# etcolor.net
KiCad netlist of a schematic drawn in EAGLE
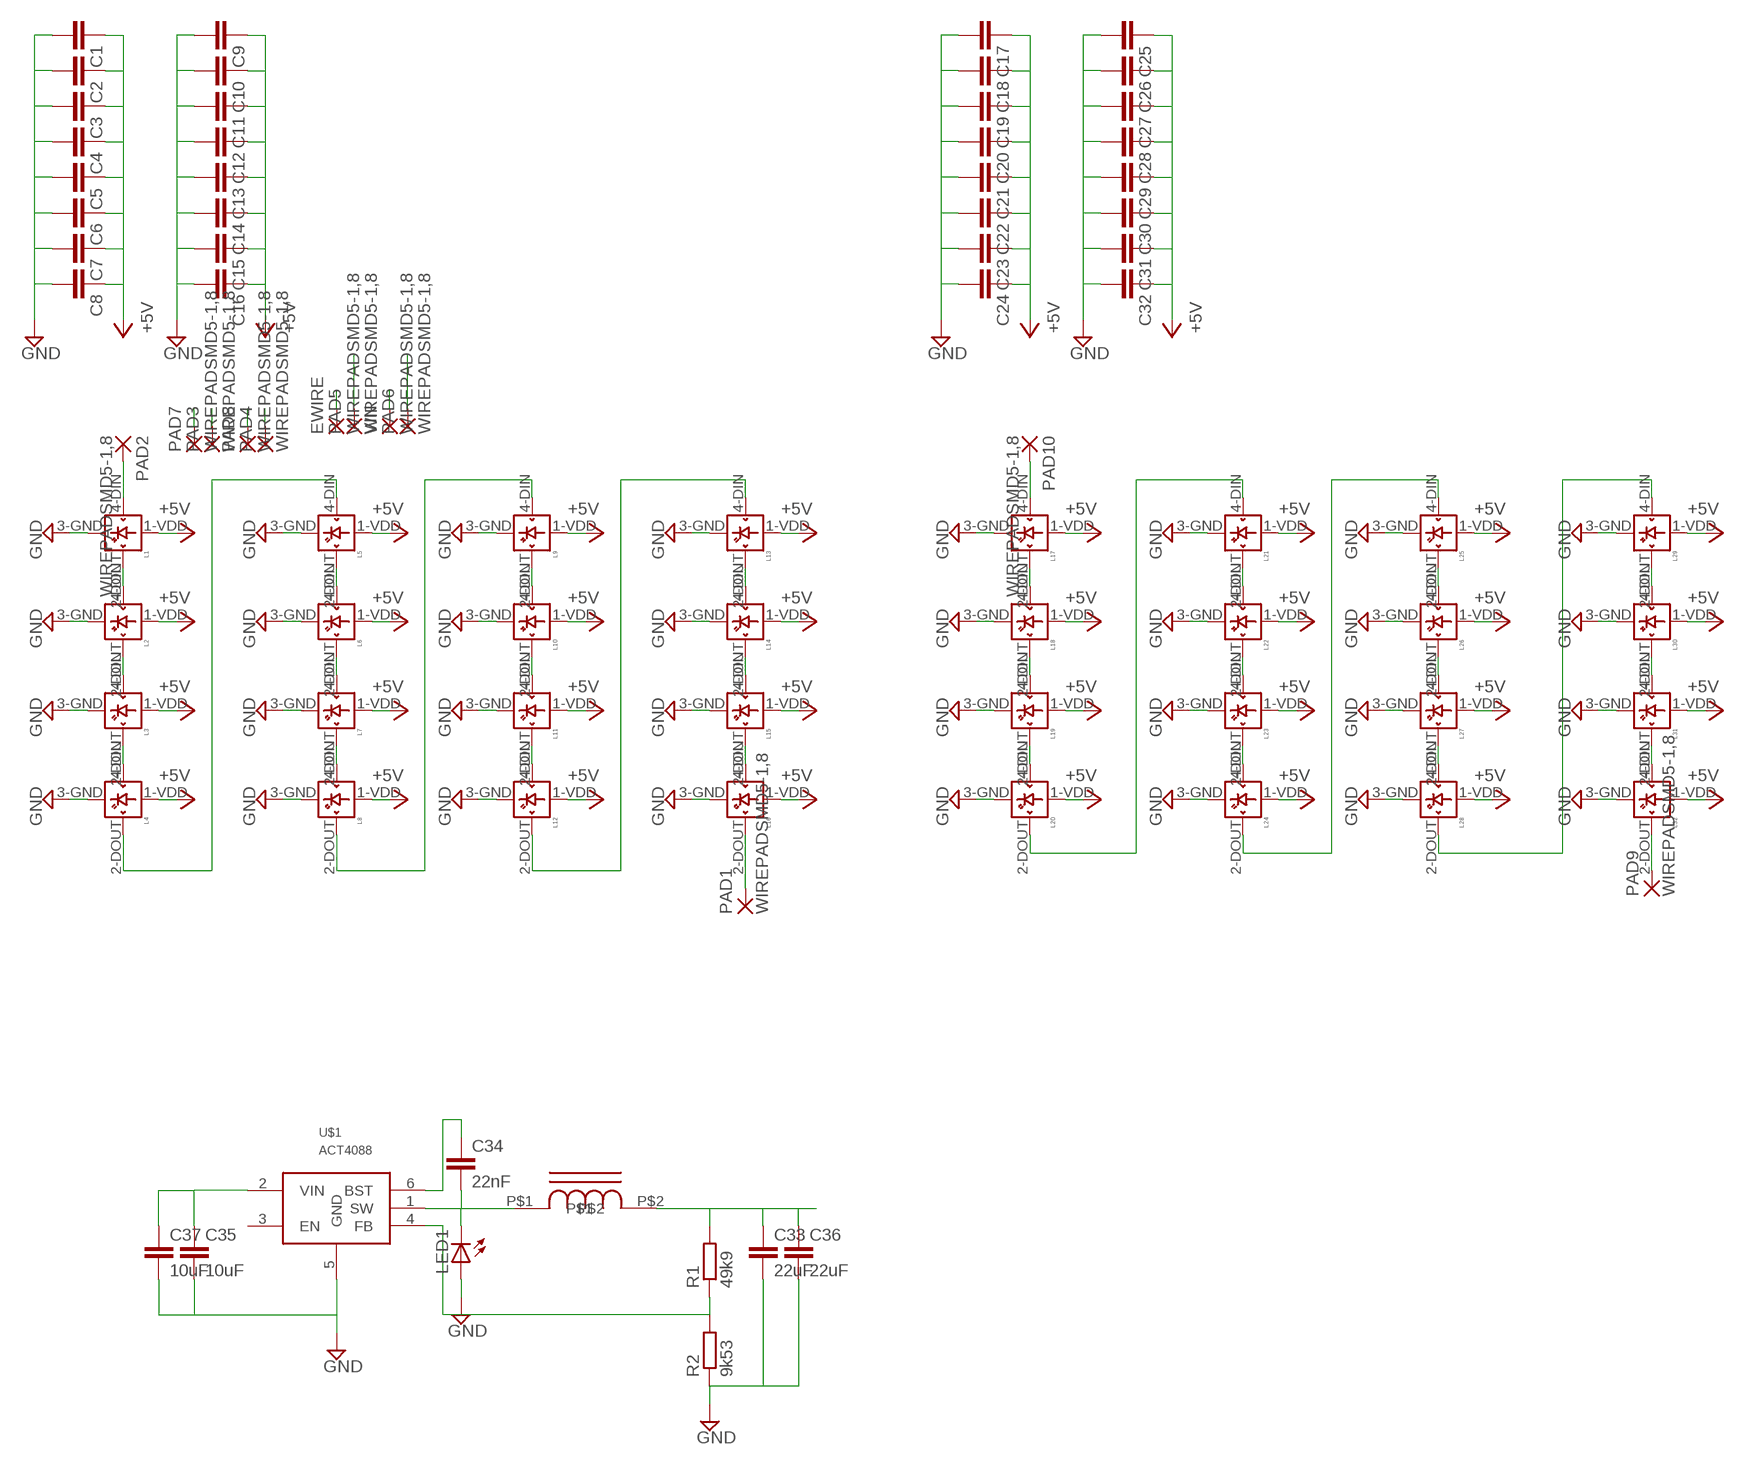
[diagram p0: schematic, sheet 1]

(export (version "E")
  (design (tool "Eeschema 10.0.6"))
  (components
    (comp (ref "C1")
      (value "C-EUC0805K")
      (footprint "eagle-import:C0805K")
      (libsource (lib "eagle-import") (part "resistor_C-EUC0805K"))
    )
    (comp (ref "C2")
      (value "C-EUC0805K")
      (footprint "eagle-import:C0805K")
      (libsource (lib "eagle-import") (part "resistor_C-EUC0805K"))
    )
    (comp (ref "C3")
      (value "C-EUC0805K")
      (footprint "eagle-import:C0805K")
      (libsource (lib "eagle-import") (part "resistor_C-EUC0805K"))
    )
    (comp (ref "C4")
      (value "C-EUC0805K")
      (footprint "eagle-import:C0805K")
      (libsource (lib "eagle-import") (part "resistor_C-EUC0805K"))
    )
    (comp (ref "C5")
      (value "C-EUC0805K")
      (footprint "eagle-import:C0805K")
      (libsource (lib "eagle-import") (part "resistor_C-EUC0805K"))
    )
    (comp (ref "C6")
      (value "C-EUC0805K")
      (footprint "eagle-import:C0805K")
      (libsource (lib "eagle-import") (part "resistor_C-EUC0805K"))
    )
    (comp (ref "C7")
      (value "C-EUC0805K")
      (footprint "eagle-import:C0805K")
      (libsource (lib "eagle-import") (part "resistor_C-EUC0805K"))
    )
    (comp (ref "C8")
      (value "C-EUC0805K")
      (footprint "eagle-import:C0805K")
      (libsource (lib "eagle-import") (part "resistor_C-EUC0805K"))
    )
    (comp (ref "C9")
      (value "C-EUC0805K")
      (footprint "eagle-import:C0805K")
      (libsource (lib "eagle-import") (part "resistor_C-EUC0805K"))
    )
    (comp (ref "C10")
      (value "C-EUC0805K")
      (footprint "eagle-import:C0805K")
      (libsource (lib "eagle-import") (part "resistor_C-EUC0805K"))
    )
    (comp (ref "C11")
      (value "C-EUC0805K")
      (footprint "eagle-import:C0805K")
      (libsource (lib "eagle-import") (part "resistor_C-EUC0805K"))
    )
    (comp (ref "C12")
      (value "C-EUC0805K")
      (footprint "eagle-import:C0805K")
      (libsource (lib "eagle-import") (part "resistor_C-EUC0805K"))
    )
    (comp (ref "C13")
      (value "C-EUC0805K")
      (footprint "eagle-import:C0805K")
      (libsource (lib "eagle-import") (part "resistor_C-EUC0805K"))
    )
    (comp (ref "C14")
      (value "C-EUC0805K")
      (footprint "eagle-import:C0805K")
      (libsource (lib "eagle-import") (part "resistor_C-EUC0805K"))
    )
    (comp (ref "C15")
      (value "C-EUC0805K")
      (footprint "eagle-import:C0805K")
      (libsource (lib "eagle-import") (part "resistor_C-EUC0805K"))
    )
    (comp (ref "C16")
      (value "C-EUC0805K")
      (footprint "eagle-import:C0805K")
      (libsource (lib "eagle-import") (part "resistor_C-EUC0805K"))
    )
    (comp (ref "C17")
      (value "C-EUC0805K")
      (footprint "eagle-import:C0805K")
      (libsource (lib "eagle-import") (part "resistor_C-EUC0805K"))
    )
    (comp (ref "C18")
      (value "C-EUC0805K")
      (footprint "eagle-import:C0805K")
      (libsource (lib "eagle-import") (part "resistor_C-EUC0805K"))
    )
    (comp (ref "C19")
      (value "C-EUC0805K")
      (footprint "eagle-import:C0805K")
      (libsource (lib "eagle-import") (part "resistor_C-EUC0805K"))
    )
    (comp (ref "C20")
      (value "C-EUC0805K")
      (footprint "eagle-import:C0805K")
      (libsource (lib "eagle-import") (part "resistor_C-EUC0805K"))
    )
    (comp (ref "C21")
      (value "C-EUC0805K")
      (footprint "eagle-import:C0805K")
      (libsource (lib "eagle-import") (part "resistor_C-EUC0805K"))
    )
    (comp (ref "C22")
      (value "C-EUC0805K")
      (footprint "eagle-import:C0805K")
      (libsource (lib "eagle-import") (part "resistor_C-EUC0805K"))
    )
    (comp (ref "C23")
      (value "C-EUC0805K")
      (footprint "eagle-import:C0805K")
      (libsource (lib "eagle-import") (part "resistor_C-EUC0805K"))
    )
    (comp (ref "C24")
      (value "C-EUC0805K")
      (footprint "eagle-import:C0805K")
      (libsource (lib "eagle-import") (part "resistor_C-EUC0805K"))
    )
    (comp (ref "C25")
      (value "C-EUC0805K")
      (footprint "eagle-import:C0805K")
      (libsource (lib "eagle-import") (part "resistor_C-EUC0805K"))
    )
    (comp (ref "C26")
      (value "C-EUC0805K")
      (footprint "eagle-import:C0805K")
      (libsource (lib "eagle-import") (part "resistor_C-EUC0805K"))
    )
    (comp (ref "C27")
      (value "C-EUC0805K")
      (footprint "eagle-import:C0805K")
      (libsource (lib "eagle-import") (part "resistor_C-EUC0805K"))
    )
    (comp (ref "C28")
      (value "C-EUC0805K")
      (footprint "eagle-import:C0805K")
      (libsource (lib "eagle-import") (part "resistor_C-EUC0805K"))
    )
    (comp (ref "C29")
      (value "C-EUC0805K")
      (footprint "eagle-import:C0805K")
      (libsource (lib "eagle-import") (part "resistor_C-EUC0805K"))
    )
    (comp (ref "C30")
      (value "C-EUC0805K")
      (footprint "eagle-import:C0805K")
      (libsource (lib "eagle-import") (part "resistor_C-EUC0805K"))
    )
    (comp (ref "C31")
      (value "C-EUC0805K")
      (footprint "eagle-import:C0805K")
      (libsource (lib "eagle-import") (part "resistor_C-EUC0805K"))
    )
    (comp (ref "C32")
      (value "C-EUC0805K")
      (footprint "eagle-import:C0805K")
      (libsource (lib "eagle-import") (part "resistor_C-EUC0805K"))
    )
    (comp (ref "C33")
      (value "22uF")
      (footprint "eagle-import:C1210")
      (libsource (lib "eagle-import") (part "C-EUC1210"))
    )
    (comp (ref "C34")
      (value "22nF")
      (footprint "eagle-import:C0805")
      (libsource (lib "eagle-import") (part "resistor_C-EUC0805"))
    )
    (comp (ref "C35")
      (value "10uF")
      (footprint "eagle-import:C1210")
      (libsource (lib "eagle-import") (part "C-EUC1210"))
    )
    (comp (ref "C36")
      (value "22uF")
      (footprint "eagle-import:C1210")
      (libsource (lib "eagle-import") (part "C-EUC1210"))
    )
    (comp (ref "C37")
      (value "10uF")
      (footprint "eagle-import:C1210")
      (libsource (lib "eagle-import") (part "C-EUC1210"))
    )
    (comp (ref "EWIRE")
      (value "WIREPADSMD5-1,8")
      (footprint "eagle-import:5-1,8")
      (libsource (lib "eagle-import") (part "WIREPADSMD5-1,8"))
    )
    (comp (ref "L1")
      (value "WS2812B")
      (footprint "eagle-import:WS2812B")
      (libsource (lib "eagle-import") (part "WS2812B"))
    )
    (comp (ref "L2")
      (value "WS2812B")
      (footprint "eagle-import:WS2812B")
      (libsource (lib "eagle-import") (part "WS2812B"))
    )
    (comp (ref "L3")
      (value "WS2812B")
      (footprint "eagle-import:WS2812B")
      (libsource (lib "eagle-import") (part "WS2812B"))
    )
    (comp (ref "L4")
      (value "WS2812B")
      (footprint "eagle-import:WS2812B")
      (libsource (lib "eagle-import") (part "WS2812B"))
    )
    (comp (ref "L5")
      (value "WS2812B")
      (footprint "eagle-import:WS2812B")
      (libsource (lib "eagle-import") (part "WS2812B"))
    )
    (comp (ref "L6")
      (value "WS2812B")
      (footprint "eagle-import:WS2812B")
      (libsource (lib "eagle-import") (part "WS2812B"))
    )
    (comp (ref "L7")
      (value "WS2812B")
      (footprint "eagle-import:WS2812B")
      (libsource (lib "eagle-import") (part "WS2812B"))
    )
    (comp (ref "L8")
      (value "WS2812B")
      (footprint "eagle-import:WS2812B")
      (libsource (lib "eagle-import") (part "WS2812B"))
    )
    (comp (ref "L9")
      (value "WS2812B")
      (footprint "eagle-import:WS2812B")
      (libsource (lib "eagle-import") (part "WS2812B"))
    )
    (comp (ref "L10")
      (value "WS2812B")
      (footprint "eagle-import:WS2812B")
      (libsource (lib "eagle-import") (part "WS2812B"))
    )
    (comp (ref "L11")
      (value "WS2812B")
      (footprint "eagle-import:WS2812B")
      (libsource (lib "eagle-import") (part "WS2812B"))
    )
    (comp (ref "L12")
      (value "WS2812B")
      (footprint "eagle-import:WS2812B")
      (libsource (lib "eagle-import") (part "WS2812B"))
    )
    (comp (ref "L13")
      (value "WS2812B")
      (footprint "eagle-import:WS2812B")
      (libsource (lib "eagle-import") (part "WS2812B"))
    )
    (comp (ref "L14")
      (value "WS2812B")
      (footprint "eagle-import:WS2812B")
      (libsource (lib "eagle-import") (part "WS2812B"))
    )
    (comp (ref "L15")
      (value "WS2812B")
      (footprint "eagle-import:WS2812B")
      (libsource (lib "eagle-import") (part "WS2812B"))
    )
    (comp (ref "L16")
      (value "WS2812B")
      (footprint "eagle-import:WS2812B")
      (libsource (lib "eagle-import") (part "WS2812B"))
    )
    (comp (ref "L17")
      (value "WS2812B")
      (footprint "eagle-import:WS2812B")
      (libsource (lib "eagle-import") (part "WS2812B"))
    )
    (comp (ref "L18")
      (value "WS2812B")
      (footprint "eagle-import:WS2812B")
      (libsource (lib "eagle-import") (part "WS2812B"))
    )
    (comp (ref "L19")
      (value "WS2812B")
      (footprint "eagle-import:WS2812B")
      (libsource (lib "eagle-import") (part "WS2812B"))
    )
    (comp (ref "L20")
      (value "WS2812B")
      (footprint "eagle-import:WS2812B")
      (libsource (lib "eagle-import") (part "WS2812B"))
    )
    (comp (ref "L21")
      (value "WS2812B")
      (footprint "eagle-import:WS2812B")
      (libsource (lib "eagle-import") (part "WS2812B"))
    )
    (comp (ref "L22")
      (value "WS2812B")
      (footprint "eagle-import:WS2812B")
      (libsource (lib "eagle-import") (part "WS2812B"))
    )
    (comp (ref "L23")
      (value "WS2812B")
      (footprint "eagle-import:WS2812B")
      (libsource (lib "eagle-import") (part "WS2812B"))
    )
    (comp (ref "L24")
      (value "WS2812B")
      (footprint "eagle-import:WS2812B")
      (libsource (lib "eagle-import") (part "WS2812B"))
    )
    (comp (ref "L25")
      (value "WS2812B")
      (footprint "eagle-import:WS2812B")
      (libsource (lib "eagle-import") (part "WS2812B"))
    )
    (comp (ref "L26")
      (value "WS2812B")
      (footprint "eagle-import:WS2812B")
      (libsource (lib "eagle-import") (part "WS2812B"))
    )
    (comp (ref "L27")
      (value "WS2812B")
      (footprint "eagle-import:WS2812B")
      (libsource (lib "eagle-import") (part "WS2812B"))
    )
    (comp (ref "L28")
      (value "WS2812B")
      (footprint "eagle-import:WS2812B")
      (libsource (lib "eagle-import") (part "WS2812B"))
    )
    (comp (ref "L29")
      (value "WS2812B")
      (footprint "eagle-import:WS2812B")
      (libsource (lib "eagle-import") (part "WS2812B"))
    )
    (comp (ref "L30")
      (value "WS2812B")
      (footprint "eagle-import:WS2812B")
      (libsource (lib "eagle-import") (part "WS2812B"))
    )
    (comp (ref "L31")
      (value "WS2812B")
      (footprint "eagle-import:WS2812B")
      (libsource (lib "eagle-import") (part "WS2812B"))
    )
    (comp (ref "L32")
      (value "WS2812B")
      (footprint "eagle-import:WS2812B")
      (libsource (lib "eagle-import") (part "WS2812B"))
    )
    (comp (ref "LED1")
      (value "LED1206")
      (footprint "eagle-import:LED-1206")
      (libsource (lib "eagle-import") (part "LED1206"))
    )
    (comp (ref "PAD1")
      (value "WIREPADSMD5-1,8")
      (footprint "eagle-import:5-1,8")
      (libsource (lib "eagle-import") (part "WIREPADSMD5-1,8"))
    )
    (comp (ref "PAD2")
      (value "WIREPADSMD5-1,8")
      (footprint "eagle-import:5-1,8")
      (libsource (lib "eagle-import") (part "WIREPADSMD5-1,8"))
    )
    (comp (ref "PAD3")
      (value "WIREPADSMD5-1,8")
      (footprint "eagle-import:5-1,8")
      (libsource (lib "eagle-import") (part "WIREPADSMD5-1,8"))
    )
    (comp (ref "PAD4")
      (value "WIREPADSMD5-1,8")
      (footprint "eagle-import:5-1,8")
      (libsource (lib "eagle-import") (part "WIREPADSMD5-1,8"))
    )
    (comp (ref "PAD5")
      (value "WIREPADSMD5-1,8")
      (footprint "eagle-import:5-1,8")
      (libsource (lib "eagle-import") (part "WIREPADSMD5-1,8"))
    )
    (comp (ref "PAD6")
      (value "WIREPADSMD5-1,8")
      (footprint "eagle-import:5-1,8")
      (libsource (lib "eagle-import") (part "WIREPADSMD5-1,8"))
    )
    (comp (ref "PAD7")
      (value "WIREPADSMD5-1,8")
      (footprint "eagle-import:5-1,8")
      (libsource (lib "eagle-import") (part "WIREPADSMD5-1,8"))
    )
    (comp (ref "PAD8")
      (value "WIREPADSMD5-1,8")
      (footprint "eagle-import:5-1,8")
      (libsource (lib "eagle-import") (part "WIREPADSMD5-1,8"))
    )
    (comp (ref "PAD9")
      (value "WIREPADSMD5-1,8")
      (footprint "eagle-import:5-1,8")
      (libsource (lib "eagle-import") (part "WIREPADSMD5-1,8"))
    )
    (comp (ref "PAD10")
      (value "WIREPADSMD5-1,8")
      (footprint "eagle-import:5-1,8")
      (libsource (lib "eagle-import") (part "WIREPADSMD5-1,8"))
    )
    (comp (ref "R1")
      (value "49k9")
      (footprint "eagle-import:M0805")
      (libsource (lib "eagle-import") (part "R-EU_M0805"))
    )
    (comp (ref "R2")
      (value "9k53")
      (footprint "eagle-import:M0805")
      (libsource (lib "eagle-import") (part "R-EU_M0805"))
    )
    (comp (ref "U$1")
      (value "ACT4088")
      (footprint "eagle-import:SOT23-6")
      (libsource (lib "eagle-import") (part "ACT4088"))
    )
    (comp (ref "U$2")
      (value "INDUCTOR")
      (footprint "eagle-import:6060")
      (libsource (lib "eagle-import") (part "INDUCTOR"))
    )
    (comp (ref "VIN")
      (value "WIREPADSMD5-1,8")
      (footprint "eagle-import:5-1,8")
      (libsource (lib "eagle-import") (part "WIREPADSMD5-1,8"))
    )
  )
  (nets
    (net (code "1") (name "+5V") (class "Default")
      (node (ref "C1") (pin "1") (pinfunction "1_1") (pintype "passive"))
      (node (ref "C10") (pin "1") (pinfunction "1_1") (pintype "passive"))
      (node (ref "C11") (pin "1") (pinfunction "1_1") (pintype "passive"))
      (node (ref "C12") (pin "1") (pinfunction "1_1") (pintype "passive"))
      (node (ref "C13") (pin "1") (pinfunction "1_1") (pintype "passive"))
      (node (ref "C14") (pin "1") (pinfunction "1_1") (pintype "passive"))
      (node (ref "C15") (pin "1") (pinfunction "1_1") (pintype "passive"))
      (node (ref "C16") (pin "1") (pinfunction "1_1") (pintype "passive"))
      (node (ref "C17") (pin "1") (pinfunction "1_1") (pintype "passive"))
      (node (ref "C18") (pin "1") (pinfunction "1_1") (pintype "passive"))
      (node (ref "C19") (pin "1") (pinfunction "1_1") (pintype "passive"))
      (node (ref "C2") (pin "1") (pinfunction "1_1") (pintype "passive"))
      (node (ref "C20") (pin "1") (pinfunction "1_1") (pintype "passive"))
      (node (ref "C21") (pin "1") (pinfunction "1_1") (pintype "passive"))
      (node (ref "C22") (pin "1") (pinfunction "1_1") (pintype "passive"))
      (node (ref "C23") (pin "1") (pinfunction "1_1") (pintype "passive"))
      (node (ref "C24") (pin "1") (pinfunction "1_1") (pintype "passive"))
      (node (ref "C25") (pin "1") (pinfunction "1_1") (pintype "passive"))
      (node (ref "C26") (pin "1") (pinfunction "1_1") (pintype "passive"))
      (node (ref "C27") (pin "1") (pinfunction "1_1") (pintype "passive"))
      (node (ref "C28") (pin "1") (pinfunction "1_1") (pintype "passive"))
      (node (ref "C29") (pin "1") (pinfunction "1_1") (pintype "passive"))
      (node (ref "C3") (pin "1") (pinfunction "1_1") (pintype "passive"))
      (node (ref "C30") (pin "1") (pinfunction "1_1") (pintype "passive"))
      (node (ref "C31") (pin "1") (pinfunction "1_1") (pintype "passive"))
      (node (ref "C32") (pin "1") (pinfunction "1_1") (pintype "passive"))
      (node (ref "C33") (pin "1") (pinfunction "1_1") (pintype "passive"))
      (node (ref "C36") (pin "1") (pinfunction "1_1") (pintype "passive"))
      (node (ref "C4") (pin "1") (pinfunction "1_1") (pintype "passive"))
      (node (ref "C5") (pin "1") (pinfunction "1_1") (pintype "passive"))
      (node (ref "C6") (pin "1") (pinfunction "1_1") (pintype "passive"))
      (node (ref "C7") (pin "1") (pinfunction "1_1") (pintype "passive"))
      (node (ref "C8") (pin "1") (pinfunction "1_1") (pintype "passive"))
      (node (ref "C9") (pin "1") (pinfunction "1_1") (pintype "passive"))
      (node (ref "L1") (pin "1-VDD") (pinfunction "VDD_1-VDD") (pintype "bidirectional"))
      (node (ref "L10") (pin "1-VDD") (pinfunction "VDD_1-VDD") (pintype "bidirectional"))
      (node (ref "L11") (pin "1-VDD") (pinfunction "VDD_1-VDD") (pintype "bidirectional"))
      (node (ref "L12") (pin "1-VDD") (pinfunction "VDD_1-VDD") (pintype "bidirectional"))
      (node (ref "L13") (pin "1-VDD") (pinfunction "VDD_1-VDD") (pintype "bidirectional"))
      (node (ref "L14") (pin "1-VDD") (pinfunction "VDD_1-VDD") (pintype "bidirectional"))
      (node (ref "L15") (pin "1-VDD") (pinfunction "VDD_1-VDD") (pintype "bidirectional"))
      (node (ref "L16") (pin "1-VDD") (pinfunction "VDD_1-VDD") (pintype "bidirectional"))
      (node (ref "L17") (pin "1-VDD") (pinfunction "VDD_1-VDD") (pintype "bidirectional"))
      (node (ref "L18") (pin "1-VDD") (pinfunction "VDD_1-VDD") (pintype "bidirectional"))
      (node (ref "L19") (pin "1-VDD") (pinfunction "VDD_1-VDD") (pintype "bidirectional"))
      (node (ref "L2") (pin "1-VDD") (pinfunction "VDD_1-VDD") (pintype "bidirectional"))
      (node (ref "L20") (pin "1-VDD") (pinfunction "VDD_1-VDD") (pintype "bidirectional"))
      (node (ref "L21") (pin "1-VDD") (pinfunction "VDD_1-VDD") (pintype "bidirectional"))
      (node (ref "L22") (pin "1-VDD") (pinfunction "VDD_1-VDD") (pintype "bidirectional"))
      (node (ref "L23") (pin "1-VDD") (pinfunction "VDD_1-VDD") (pintype "bidirectional"))
      (node (ref "L24") (pin "1-VDD") (pinfunction "VDD_1-VDD") (pintype "bidirectional"))
      (node (ref "L25") (pin "1-VDD") (pinfunction "VDD_1-VDD") (pintype "bidirectional"))
      (node (ref "L26") (pin "1-VDD") (pinfunction "VDD_1-VDD") (pintype "bidirectional"))
      (node (ref "L27") (pin "1-VDD") (pinfunction "VDD_1-VDD") (pintype "bidirectional"))
      (node (ref "L28") (pin "1-VDD") (pinfunction "VDD_1-VDD") (pintype "bidirectional"))
      (node (ref "L29") (pin "1-VDD") (pinfunction "VDD_1-VDD") (pintype "bidirectional"))
      (node (ref "L3") (pin "1-VDD") (pinfunction "VDD_1-VDD") (pintype "bidirectional"))
      (node (ref "L30") (pin "1-VDD") (pinfunction "VDD_1-VDD") (pintype "bidirectional"))
      (node (ref "L31") (pin "1-VDD") (pinfunction "VDD_1-VDD") (pintype "bidirectional"))
      (node (ref "L32") (pin "1-VDD") (pinfunction "VDD_1-VDD") (pintype "bidirectional"))
      (node (ref "L4") (pin "1-VDD") (pinfunction "VDD_1-VDD") (pintype "bidirectional"))
      (node (ref "L5") (pin "1-VDD") (pinfunction "VDD_1-VDD") (pintype "bidirectional"))
      (node (ref "L6") (pin "1-VDD") (pinfunction "VDD_1-VDD") (pintype "bidirectional"))
      (node (ref "L7") (pin "1-VDD") (pinfunction "VDD_1-VDD") (pintype "bidirectional"))
      (node (ref "L8") (pin "1-VDD") (pinfunction "VDD_1-VDD") (pintype "bidirectional"))
      (node (ref "L9") (pin "1-VDD") (pinfunction "VDD_1-VDD") (pintype "bidirectional"))
      (node (ref "R1") (pin "2") (pinfunction "2_2") (pintype "passive"))
      (node (ref "U$2") (pin "P$2") (pinfunction "P$2_P$2") (pintype "bidirectional"))
    )
    (net (code "2") (name "/VIN") (class "Default")
      (node (ref "C35") (pin "1") (pinfunction "1_1") (pintype "passive"))
      (node (ref "C37") (pin "1") (pinfunction "1_1") (pintype "passive"))
      (node (ref "EWIRE") (pin "1") (pinfunction "P_1") (pintype "passive"))
      (node (ref "PAD5") (pin "1") (pinfunction "P_1") (pintype "passive"))
      (node (ref "PAD6") (pin "1") (pinfunction "P_1") (pintype "passive"))
      (node (ref "U$1") (pin "2") (pinfunction "VIN_2") (pintype "bidirectional"))
      (node (ref "VIN") (pin "1") (pinfunction "P_1") (pintype "passive"))
    )
    (net (code "3") (name "GND") (class "Default")
      (node (ref "C1") (pin "2") (pinfunction "2_2") (pintype "passive"))
      (node (ref "C10") (pin "2") (pinfunction "2_2") (pintype "passive"))
      (node (ref "C11") (pin "2") (pinfunction "2_2") (pintype "passive"))
      (node (ref "C12") (pin "2") (pinfunction "2_2") (pintype "passive"))
      (node (ref "C13") (pin "2") (pinfunction "2_2") (pintype "passive"))
      (node (ref "C14") (pin "2") (pinfunction "2_2") (pintype "passive"))
      (node (ref "C15") (pin "2") (pinfunction "2_2") (pintype "passive"))
      (node (ref "C16") (pin "2") (pinfunction "2_2") (pintype "passive"))
      (node (ref "C17") (pin "2") (pinfunction "2_2") (pintype "passive"))
      (node (ref "C18") (pin "2") (pinfunction "2_2") (pintype "passive"))
      (node (ref "C19") (pin "2") (pinfunction "2_2") (pintype "passive"))
      (node (ref "C2") (pin "2") (pinfunction "2_2") (pintype "passive"))
      (node (ref "C20") (pin "2") (pinfunction "2_2") (pintype "passive"))
      (node (ref "C21") (pin "2") (pinfunction "2_2") (pintype "passive"))
      (node (ref "C22") (pin "2") (pinfunction "2_2") (pintype "passive"))
      (node (ref "C23") (pin "2") (pinfunction "2_2") (pintype "passive"))
      (node (ref "C24") (pin "2") (pinfunction "2_2") (pintype "passive"))
      (node (ref "C25") (pin "2") (pinfunction "2_2") (pintype "passive"))
      (node (ref "C26") (pin "2") (pinfunction "2_2") (pintype "passive"))
      (node (ref "C27") (pin "2") (pinfunction "2_2") (pintype "passive"))
      (node (ref "C28") (pin "2") (pinfunction "2_2") (pintype "passive"))
      (node (ref "C29") (pin "2") (pinfunction "2_2") (pintype "passive"))
      (node (ref "C3") (pin "2") (pinfunction "2_2") (pintype "passive"))
      (node (ref "C30") (pin "2") (pinfunction "2_2") (pintype "passive"))
      (node (ref "C31") (pin "2") (pinfunction "2_2") (pintype "passive"))
      (node (ref "C32") (pin "2") (pinfunction "2_2") (pintype "passive"))
      (node (ref "C33") (pin "2") (pinfunction "2_2") (pintype "passive"))
      (node (ref "C35") (pin "2") (pinfunction "2_2") (pintype "passive"))
      (node (ref "C36") (pin "2") (pinfunction "2_2") (pintype "passive"))
      (node (ref "C37") (pin "2") (pinfunction "2_2") (pintype "passive"))
      (node (ref "C4") (pin "2") (pinfunction "2_2") (pintype "passive"))
      (node (ref "C5") (pin "2") (pinfunction "2_2") (pintype "passive"))
      (node (ref "C6") (pin "2") (pinfunction "2_2") (pintype "passive"))
      (node (ref "C7") (pin "2") (pinfunction "2_2") (pintype "passive"))
      (node (ref "C8") (pin "2") (pinfunction "2_2") (pintype "passive"))
      (node (ref "C9") (pin "2") (pinfunction "2_2") (pintype "passive"))
      (node (ref "L1") (pin "3-GND") (pinfunction "GND_3-GND") (pintype "bidirectional"))
      (node (ref "L10") (pin "3-GND") (pinfunction "GND_3-GND") (pintype "bidirectional"))
      (node (ref "L11") (pin "3-GND") (pinfunction "GND_3-GND") (pintype "bidirectional"))
      (node (ref "L12") (pin "3-GND") (pinfunction "GND_3-GND") (pintype "bidirectional"))
      (node (ref "L13") (pin "3-GND") (pinfunction "GND_3-GND") (pintype "bidirectional"))
      (node (ref "L14") (pin "3-GND") (pinfunction "GND_3-GND") (pintype "bidirectional"))
      (node (ref "L15") (pin "3-GND") (pinfunction "GND_3-GND") (pintype "bidirectional"))
      (node (ref "L16") (pin "3-GND") (pinfunction "GND_3-GND") (pintype "bidirectional"))
      (node (ref "L17") (pin "3-GND") (pinfunction "GND_3-GND") (pintype "bidirectional"))
      (node (ref "L18") (pin "3-GND") (pinfunction "GND_3-GND") (pintype "bidirectional"))
      (node (ref "L19") (pin "3-GND") (pinfunction "GND_3-GND") (pintype "bidirectional"))
      (node (ref "L2") (pin "3-GND") (pinfunction "GND_3-GND") (pintype "bidirectional"))
      (node (ref "L20") (pin "3-GND") (pinfunction "GND_3-GND") (pintype "bidirectional"))
      (node (ref "L21") (pin "3-GND") (pinfunction "GND_3-GND") (pintype "bidirectional"))
      (node (ref "L22") (pin "3-GND") (pinfunction "GND_3-GND") (pintype "bidirectional"))
      (node (ref "L23") (pin "3-GND") (pinfunction "GND_3-GND") (pintype "bidirectional"))
      (node (ref "L24") (pin "3-GND") (pinfunction "GND_3-GND") (pintype "bidirectional"))
      (node (ref "L25") (pin "3-GND") (pinfunction "GND_3-GND") (pintype "bidirectional"))
      (node (ref "L26") (pin "3-GND") (pinfunction "GND_3-GND") (pintype "bidirectional"))
      (node (ref "L27") (pin "3-GND") (pinfunction "GND_3-GND") (pintype "bidirectional"))
      (node (ref "L28") (pin "3-GND") (pinfunction "GND_3-GND") (pintype "bidirectional"))
      (node (ref "L29") (pin "3-GND") (pinfunction "GND_3-GND") (pintype "bidirectional"))
      (node (ref "L3") (pin "3-GND") (pinfunction "GND_3-GND") (pintype "bidirectional"))
      (node (ref "L30") (pin "3-GND") (pinfunction "GND_3-GND") (pintype "bidirectional"))
      (node (ref "L31") (pin "3-GND") (pinfunction "GND_3-GND") (pintype "bidirectional"))
      (node (ref "L32") (pin "3-GND") (pinfunction "GND_3-GND") (pintype "bidirectional"))
      (node (ref "L4") (pin "3-GND") (pinfunction "GND_3-GND") (pintype "bidirectional"))
      (node (ref "L5") (pin "3-GND") (pinfunction "GND_3-GND") (pintype "bidirectional"))
      (node (ref "L6") (pin "3-GND") (pinfunction "GND_3-GND") (pintype "bidirectional"))
      (node (ref "L7") (pin "3-GND") (pinfunction "GND_3-GND") (pintype "bidirectional"))
      (node (ref "L8") (pin "3-GND") (pinfunction "GND_3-GND") (pintype "bidirectional"))
      (node (ref "L9") (pin "3-GND") (pinfunction "GND_3-GND") (pintype "bidirectional"))
      (node (ref "LED1") (pin "A") (pinfunction "A_A") (pintype "passive"))
      (node (ref "PAD3") (pin "1") (pinfunction "P_1") (pintype "passive"))
      (node (ref "PAD4") (pin "1") (pinfunction "P_1") (pintype "passive"))
      (node (ref "PAD7") (pin "1") (pinfunction "P_1") (pintype "passive"))
      (node (ref "PAD8") (pin "1") (pinfunction "P_1") (pintype "passive"))
      (node (ref "R2") (pin "1") (pinfunction "1_1") (pintype "passive"))
      (node (ref "U$1") (pin "5") (pinfunction "GND_5") (pintype "bidirectional"))
    )
    (net (code "4") (name "Net-(L1-DIN)") (class "Default")
      (node (ref "L1") (pin "4-DIN") (pinfunction "DIN_4-DIN") (pintype "input"))
      (node (ref "PAD2") (pin "1") (pinfunction "P_1") (pintype "passive"))
    )
    (net (code "5") (name "Net-(L1-DOUT)") (class "Default")
      (node (ref "L1") (pin "2-DOUT") (pinfunction "DOUT_2-DOUT") (pintype "output"))
      (node (ref "L2") (pin "4-DIN") (pinfunction "DIN_4-DIN") (pintype "input"))
    )
    (net (code "6") (name "Net-(L2-DOUT)") (class "Default")
      (node (ref "L2") (pin "2-DOUT") (pinfunction "DOUT_2-DOUT") (pintype "output"))
      (node (ref "L3") (pin "4-DIN") (pinfunction "DIN_4-DIN") (pintype "input"))
    )
    (net (code "7") (name "Net-(L3-DOUT)") (class "Default")
      (node (ref "L3") (pin "2-DOUT") (pinfunction "DOUT_2-DOUT") (pintype "output"))
      (node (ref "L4") (pin "4-DIN") (pinfunction "DIN_4-DIN") (pintype "input"))
    )
    (net (code "8") (name "Net-(L4-DOUT)") (class "Default")
      (node (ref "L4") (pin "2-DOUT") (pinfunction "DOUT_2-DOUT") (pintype "output"))
      (node (ref "L5") (pin "4-DIN") (pinfunction "DIN_4-DIN") (pintype "input"))
    )
    (net (code "9") (name "Net-(L5-DOUT)") (class "Default")
      (node (ref "L5") (pin "2-DOUT") (pinfunction "DOUT_2-DOUT") (pintype "output"))
      (node (ref "L6") (pin "4-DIN") (pinfunction "DIN_4-DIN") (pintype "input"))
    )
    (net (code "10") (name "Net-(L6-DOUT)") (class "Default")
      (node (ref "L6") (pin "2-DOUT") (pinfunction "DOUT_2-DOUT") (pintype "output"))
      (node (ref "L7") (pin "4-DIN") (pinfunction "DIN_4-DIN") (pintype "input"))
    )
    (net (code "11") (name "Net-(L7-DOUT)") (class "Default")
      (node (ref "L7") (pin "2-DOUT") (pinfunction "DOUT_2-DOUT") (pintype "output"))
      (node (ref "L8") (pin "4-DIN") (pinfunction "DIN_4-DIN") (pintype "input"))
    )
    (net (code "12") (name "Net-(L8-DOUT)") (class "Default")
      (node (ref "L8") (pin "2-DOUT") (pinfunction "DOUT_2-DOUT") (pintype "output"))
      (node (ref "L9") (pin "4-DIN") (pinfunction "DIN_4-DIN") (pintype "input"))
    )
    (net (code "13") (name "Net-(L10-DIN)") (class "Default")
      (node (ref "L10") (pin "4-DIN") (pinfunction "DIN_4-DIN") (pintype "input"))
      (node (ref "L9") (pin "2-DOUT") (pinfunction "DOUT_2-DOUT") (pintype "output"))
    )
    (net (code "14") (name "Net-(L10-DOUT)") (class "Default")
      (node (ref "L10") (pin "2-DOUT") (pinfunction "DOUT_2-DOUT") (pintype "output"))
      (node (ref "L11") (pin "4-DIN") (pinfunction "DIN_4-DIN") (pintype "input"))
    )
    (net (code "15") (name "Net-(L11-DOUT)") (class "Default")
      (node (ref "L11") (pin "2-DOUT") (pinfunction "DOUT_2-DOUT") (pintype "output"))
      (node (ref "L12") (pin "4-DIN") (pinfunction "DIN_4-DIN") (pintype "input"))
    )
    (net (code "16") (name "Net-(L12-DOUT)") (class "Default")
      (node (ref "L12") (pin "2-DOUT") (pinfunction "DOUT_2-DOUT") (pintype "output"))
      (node (ref "L13") (pin "4-DIN") (pinfunction "DIN_4-DIN") (pintype "input"))
    )
    (net (code "17") (name "Net-(L13-DOUT)") (class "Default")
      (node (ref "L13") (pin "2-DOUT") (pinfunction "DOUT_2-DOUT") (pintype "output"))
      (node (ref "L14") (pin "4-DIN") (pinfunction "DIN_4-DIN") (pintype "input"))
    )
    (net (code "18") (name "Net-(L14-DOUT)") (class "Default")
      (node (ref "L14") (pin "2-DOUT") (pinfunction "DOUT_2-DOUT") (pintype "output"))
      (node (ref "L15") (pin "4-DIN") (pinfunction "DIN_4-DIN") (pintype "input"))
    )
    (net (code "19") (name "Net-(L15-DOUT)") (class "Default")
      (node (ref "L15") (pin "2-DOUT") (pinfunction "DOUT_2-DOUT") (pintype "output"))
      (node (ref "L16") (pin "4-DIN") (pinfunction "DIN_4-DIN") (pintype "input"))
    )
    (net (code "20") (name "Net-(L16-DOUT)") (class "Default")
      (node (ref "L16") (pin "2-DOUT") (pinfunction "DOUT_2-DOUT") (pintype "output"))
      (node (ref "PAD1") (pin "1") (pinfunction "P_1") (pintype "passive"))
    )
    (net (code "21") (name "Net-(L17-DIN)") (class "Default")
      (node (ref "L17") (pin "4-DIN") (pinfunction "DIN_4-DIN") (pintype "input"))
      (node (ref "PAD10") (pin "1") (pinfunction "P_1") (pintype "passive"))
    )
    (net (code "22") (name "Net-(L17-DOUT)") (class "Default")
      (node (ref "L17") (pin "2-DOUT") (pinfunction "DOUT_2-DOUT") (pintype "output"))
      (node (ref "L18") (pin "4-DIN") (pinfunction "DIN_4-DIN") (pintype "input"))
    )
    (net (code "23") (name "Net-(L18-DOUT)") (class "Default")
      (node (ref "L18") (pin "2-DOUT") (pinfunction "DOUT_2-DOUT") (pintype "output"))
      (node (ref "L19") (pin "4-DIN") (pinfunction "DIN_4-DIN") (pintype "input"))
    )
    (net (code "24") (name "Net-(L19-DOUT)") (class "Default")
      (node (ref "L19") (pin "2-DOUT") (pinfunction "DOUT_2-DOUT") (pintype "output"))
      (node (ref "L20") (pin "4-DIN") (pinfunction "DIN_4-DIN") (pintype "input"))
    )
    (net (code "25") (name "Net-(L20-DOUT)") (class "Default")
      (node (ref "L20") (pin "2-DOUT") (pinfunction "DOUT_2-DOUT") (pintype "output"))
      (node (ref "L21") (pin "4-DIN") (pinfunction "DIN_4-DIN") (pintype "input"))
    )
    (net (code "26") (name "Net-(L21-DOUT)") (class "Default")
      (node (ref "L21") (pin "2-DOUT") (pinfunction "DOUT_2-DOUT") (pintype "output"))
      (node (ref "L22") (pin "4-DIN") (pinfunction "DIN_4-DIN") (pintype "input"))
    )
    (net (code "27") (name "Net-(L22-DOUT)") (class "Default")
      (node (ref "L22") (pin "2-DOUT") (pinfunction "DOUT_2-DOUT") (pintype "output"))
      (node (ref "L23") (pin "4-DIN") (pinfunction "DIN_4-DIN") (pintype "input"))
    )
    (net (code "28") (name "Net-(L23-DOUT)") (class "Default")
      (node (ref "L23") (pin "2-DOUT") (pinfunction "DOUT_2-DOUT") (pintype "output"))
      (node (ref "L24") (pin "4-DIN") (pinfunction "DIN_4-DIN") (pintype "input"))
    )
    (net (code "29") (name "Net-(L24-DOUT)") (class "Default")
      (node (ref "L24") (pin "2-DOUT") (pinfunction "DOUT_2-DOUT") (pintype "output"))
      (node (ref "L25") (pin "4-DIN") (pinfunction "DIN_4-DIN") (pintype "input"))
    )
    (net (code "30") (name "Net-(L25-DOUT)") (class "Default")
      (node (ref "L25") (pin "2-DOUT") (pinfunction "DOUT_2-DOUT") (pintype "output"))
      (node (ref "L26") (pin "4-DIN") (pinfunction "DIN_4-DIN") (pintype "input"))
    )
    (net (code "31") (name "Net-(L26-DOUT)") (class "Default")
      (node (ref "L26") (pin "2-DOUT") (pinfunction "DOUT_2-DOUT") (pintype "output"))
      (node (ref "L27") (pin "4-DIN") (pinfunction "DIN_4-DIN") (pintype "input"))
    )
    (net (code "32") (name "Net-(L27-DOUT)") (class "Default")
      (node (ref "L27") (pin "2-DOUT") (pinfunction "DOUT_2-DOUT") (pintype "output"))
      (node (ref "L28") (pin "4-DIN") (pinfunction "DIN_4-DIN") (pintype "input"))
    )
    (net (code "33") (name "Net-(L28-DOUT)") (class "Default")
      (node (ref "L28") (pin "2-DOUT") (pinfunction "DOUT_2-DOUT") (pintype "output"))
      (node (ref "L29") (pin "4-DIN") (pinfunction "DIN_4-DIN") (pintype "input"))
    )
    (net (code "34") (name "Net-(L29-DOUT)") (class "Default")
      (node (ref "L29") (pin "2-DOUT") (pinfunction "DOUT_2-DOUT") (pintype "output"))
      (node (ref "L30") (pin "4-DIN") (pinfunction "DIN_4-DIN") (pintype "input"))
    )
    (net (code "35") (name "Net-(L30-DOUT)") (class "Default")
      (node (ref "L30") (pin "2-DOUT") (pinfunction "DOUT_2-DOUT") (pintype "output"))
      (node (ref "L31") (pin "4-DIN") (pinfunction "DIN_4-DIN") (pintype "input"))
    )
    (net (code "36") (name "Net-(L31-DOUT)") (class "Default")
      (node (ref "L31") (pin "2-DOUT") (pinfunction "DOUT_2-DOUT") (pintype "output"))
      (node (ref "L32") (pin "4-DIN") (pinfunction "DIN_4-DIN") (pintype "input"))
    )
    (net (code "37") (name "Net-(L32-DOUT)") (class "Default")
      (node (ref "L32") (pin "2-DOUT") (pinfunction "DOUT_2-DOUT") (pintype "output"))
      (node (ref "PAD9") (pin "1") (pinfunction "P_1") (pintype "passive"))
    )
    (net (code "38") (name "Net-(U$1-BST)") (class "Default")
      (node (ref "C34") (pin "1") (pinfunction "1_1") (pintype "passive"))
      (node (ref "U$1") (pin "6") (pinfunction "BST_6") (pintype "bidirectional"))
    )
    (net (code "39") (name "Net-(U$1-FB)") (class "Default")
      (node (ref "R1") (pin "1") (pinfunction "1_1") (pintype "passive"))
      (node (ref "R2") (pin "2") (pinfunction "2_2") (pintype "passive"))
      (node (ref "U$1") (pin "4") (pinfunction "FB_4") (pintype "bidirectional"))
    )
    (net (code "40") (name "Net-(U$1-SW)") (class "Default")
      (node (ref "C34") (pin "2") (pinfunction "2_2") (pintype "passive"))
      (node (ref "LED1") (pin "C") (pinfunction "C_C") (pintype "passive"))
      (node (ref "U$1") (pin "1") (pinfunction "SW_1") (pintype "bidirectional"))
      (node (ref "U$2") (pin "P$1") (pinfunction "P$1_P$1") (pintype "bidirectional"))
    )
    (net (code "41") (name "unconnected-(U$1-EN-Pad3)") (class "Default")
      (node (ref "U$1") (pin "3") (pinfunction "EN_3") (pintype "bidirectional"))
    )
  )
)
